# nano.net
KiCad netlist of a schematic drawn in EAGLE
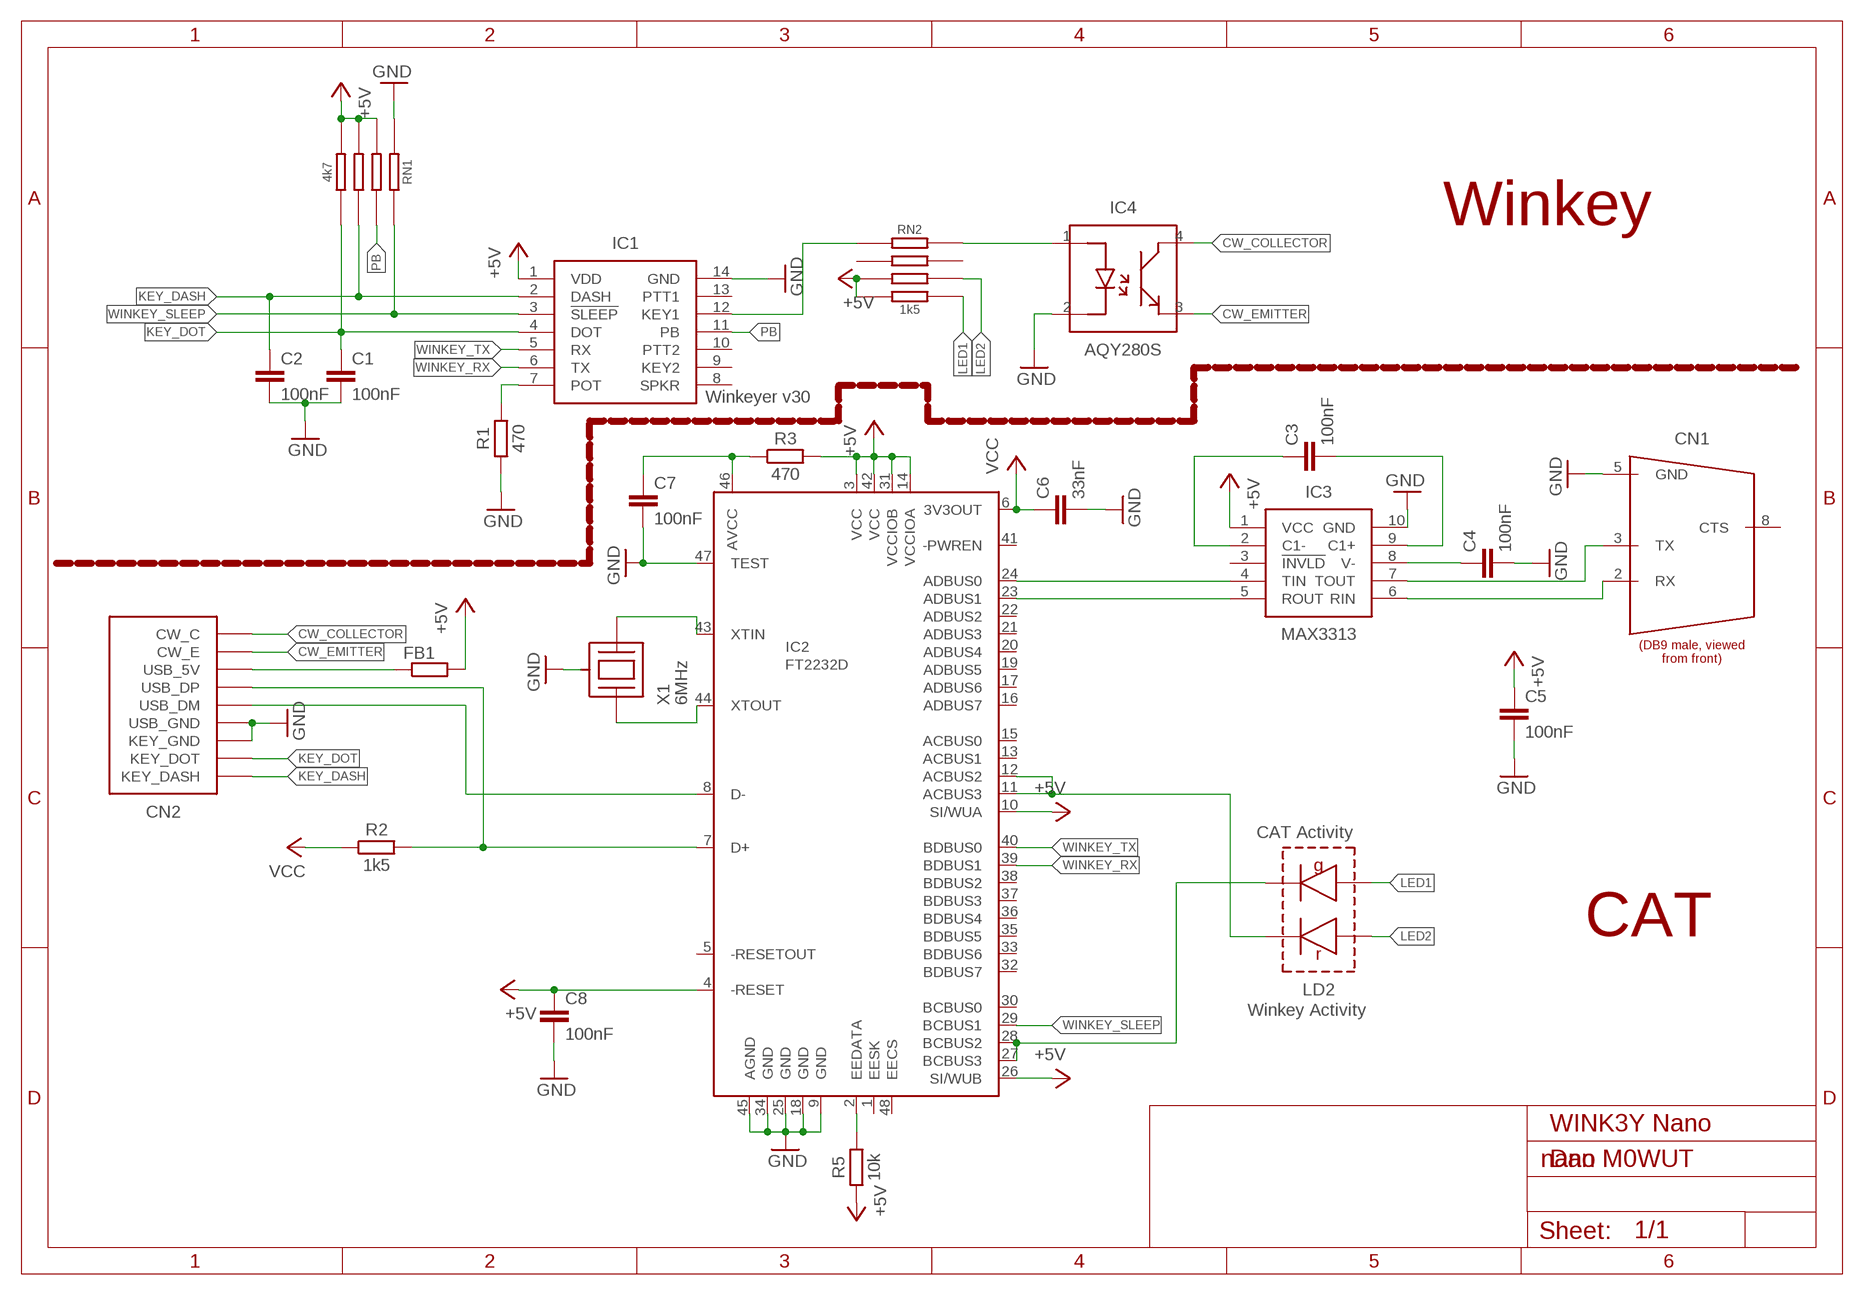
[diagram p0: schematic, sheet 1]

(export (version "E")
  (design (tool "Eeschema 10.0.6"))
  (components
    (comp (ref "C1")
      (value "100nF")
      (footprint "eagle-import:C0402")
      (libsource (lib "eagle-import") (part "C-EUC0402"))
    )
    (comp (ref "C2")
      (value "100nF")
      (footprint "eagle-import:C0402")
      (libsource (lib "eagle-import") (part "C-EUC0402"))
    )
    (comp (ref "C3")
      (value "100nF")
      (footprint "eagle-import:C0402")
      (libsource (lib "eagle-import") (part "C-EUC0402"))
    )
    (comp (ref "C4")
      (value "100nF")
      (footprint "eagle-import:C0402")
      (libsource (lib "eagle-import") (part "C-EUC0402"))
    )
    (comp (ref "C5")
      (value "100nF")
      (footprint "eagle-import:C0402")
      (libsource (lib "eagle-import") (part "C-EUC0402"))
    )
    (comp (ref "C6")
      (value "33nF")
      (footprint "eagle-import:C0402")
      (libsource (lib "eagle-import") (part "C-EUC0402"))
    )
    (comp (ref "C7")
      (value "100nF")
      (footprint "eagle-import:C0402")
      (libsource (lib "eagle-import") (part "C-EUC0402"))
    )
    (comp (ref "C8")
      (value "100nF")
      (footprint "eagle-import:C0402")
      (libsource (lib "eagle-import") (part "C-EUC0402"))
    )
    (comp (ref "CN1")
      (value "CONN_DB9_MALE")
      (footprint "eagle-import:CONN_DB9")
      (libsource (lib "eagle-import") (part "CONN_DB9_MALE"))
    )
    (comp (ref "CN2")
      (value "CONN_WINK3Y")
      (footprint "eagle-import:CONN_2MMX9")
      (libsource (lib "eagle-import") (part "CONN_WINK3Y"))
    )
    (comp (ref "FB1")
      (value "R-EU_R0805")
      (footprint "eagle-import:R0805")
      (libsource (lib "eagle-import") (part "resistor_R-EU_R0805"))
    )
    (comp (ref "IC1")
      (value "WINKEYER")
      (footprint "eagle-import:SO14")
      (libsource (lib "eagle-import") (part "WINKEYER"))
    )
    (comp (ref "IC2")
      (value "FT2232D")
      (footprint "eagle-import:QFP48-7X7")
      (libsource (lib "eagle-import") (part "FT2232D"))
    )
    (comp (ref "IC3")
      (value "IC_MAX3313")
      (footprint "eagle-import:IC_UMAX10")
      (libsource (lib "eagle-import") (part "IC_MAX3313"))
    )
    (comp (ref "IC4")
      (value "IC_AQY280S")
      (footprint "eagle-import:IC_AQY280S")
      (libsource (lib "eagle-import") (part "IC_AQY280S"))
    )
    (comp (ref "LD2")
      (value "LED_KINGBRIGHT_KPTB")
      (footprint "eagle-import:LED_KINGBRIGHT_KPTB")
      (libsource (lib "eagle-import") (part "LED_KINGBRIGHT_KPTB"))
    )
    (comp (ref "R1")
      (value "470")
      (footprint "eagle-import:R0402")
      (libsource (lib "eagle-import") (part "R-EU_R0402"))
    )
    (comp (ref "R2")
      (value "1k5")
      (footprint "eagle-import:R0402")
      (libsource (lib "eagle-import") (part "R-EU_R0402"))
    )
    (comp (ref "R3")
      (value "470")
      (footprint "eagle-import:R0402")
      (libsource (lib "eagle-import") (part "R-EU_R0402"))
    )
    (comp (ref "R5")
      (value "10k")
      (footprint "eagle-import:R0402")
      (libsource (lib "eagle-import") (part "R-EU_R0402"))
    )
    (comp (ref "RN1")
      (value "4k7")
      (footprint "eagle-import:R_BOURNS_CAY16-J4")
      (libsource (lib "eagle-import") (part "R_BOURNS_CAY16-J4"))
    )
    (comp (ref "RN2")
      (value "1k5")
      (footprint "eagle-import:R_BOURNS_CAY16-J4")
      (libsource (lib "eagle-import") (part "R_BOURNS_CAY16-J4"))
    )
    (comp (ref "X1")
      (value "6MHz")
      (footprint "eagle-import:XTAL_MURATA_3-PIN-RES")
      (libsource (lib "eagle-import") (part "XTAL_MURATA_3-PIN-RES"))
    )
  )
  (nets
    (net (code "1") (name "+5V") (class "Default")
      (node (ref "C5") (pin "1") (pinfunction "1_1") (pintype "passive"))
      (node (ref "C8") (pin "1") (pinfunction "1_1") (pintype "passive"))
      (node (ref "FB1") (pin "2") (pinfunction "2_2") (pintype "passive"))
      (node (ref "IC1") (pin "1") (pinfunction "VDD_1") (pintype "bidirectional"))
      (node (ref "IC2") (pin "10") (pinfunction "SI/WUA_10") (pintype "bidirectional"))
      (node (ref "IC2") (pin "14") (pinfunction "VCCIOA_14") (pintype "power_in"))
      (node (ref "IC2") (pin "26") (pinfunction "SI/WUB_26") (pintype "bidirectional"))
      (node (ref "IC2") (pin "3") (pinfunction "VCC_3") (pintype "power_in"))
      (node (ref "IC2") (pin "31") (pinfunction "VCCIOB_31") (pintype "power_in"))
      (node (ref "IC2") (pin "4") (pinfunction "-RESET_4") (pintype "input"))
      (node (ref "IC2") (pin "42") (pinfunction "VCC_42") (pintype "power_in"))
      (node (ref "IC3") (pin "1") (pinfunction "VCC_1") (pintype "bidirectional"))
      (node (ref "R3") (pin "2") (pinfunction "2_2") (pintype "passive"))
      (node (ref "R5") (pin "1") (pinfunction "1_1") (pintype "passive"))
      (node (ref "RN1") (pin "2") (pinfunction "2_2") (pintype "bidirectional"))
      (node (ref "RN1") (pin "3") (pinfunction "3_3") (pintype "bidirectional"))
      (node (ref "RN1") (pin "4") (pinfunction "4_4") (pintype "bidirectional"))
      (node (ref "RN2") (pin "3") (pinfunction "3_3") (pintype "bidirectional"))
      (node (ref "RN2") (pin "4") (pinfunction "4_4") (pintype "bidirectional"))
    )
    (net (code "2") (name "CW_COLLECTOR") (class "Default")
      (node (ref "CN2") (pin "CW_COLLECTOR") (pinfunction "CW_C_CW_COLLECTOR") (pintype "bidirectional"))
      (node (ref "IC4") (pin "4") (pinfunction "COLLECTOR_4") (pintype "bidirectional"))
    )
    (net (code "3") (name "CW_EMITTER") (class "Default")
      (node (ref "CN2") (pin "CW_EMITTER") (pinfunction "CW_E_CW_EMITTER") (pintype "bidirectional"))
      (node (ref "IC4") (pin "3") (pinfunction "EMITTER_3") (pintype "bidirectional"))
    )
    (net (code "4") (name "GND") (class "Default")
      (node (ref "C1") (pin "2") (pinfunction "2_2") (pintype "passive"))
      (node (ref "C2") (pin "2") (pinfunction "2_2") (pintype "passive"))
      (node (ref "C4") (pin "2") (pinfunction "2_2") (pintype "passive"))
      (node (ref "C5") (pin "2") (pinfunction "2_2") (pintype "passive"))
      (node (ref "C6") (pin "2") (pinfunction "2_2") (pintype "passive"))
      (node (ref "C7") (pin "2") (pinfunction "2_2") (pintype "passive"))
      (node (ref "C8") (pin "2") (pinfunction "2_2") (pintype "passive"))
      (node (ref "CN1") (pin "5") (pinfunction "GND_5") (pintype "bidirectional"))
      (node (ref "CN2") (pin "KEY_GND") (pinfunction "KEY_GND_KEY_GND") (pintype "bidirectional"))
      (node (ref "CN2") (pin "USB_GND") (pinfunction "USB_GND_USB_GND") (pintype "bidirectional"))
      (node (ref "IC1") (pin "14") (pinfunction "GND_14") (pintype "bidirectional"))
      (node (ref "IC2") (pin "18") (pinfunction "GND_18") (pintype "power_in"))
      (node (ref "IC2") (pin "25") (pinfunction "GND_25") (pintype "power_in"))
      (node (ref "IC2") (pin "34") (pinfunction "GND_34") (pintype "power_in"))
      (node (ref "IC2") (pin "45") (pinfunction "AGND_45") (pintype "power_in"))
      (node (ref "IC2") (pin "47") (pinfunction "TEST_47") (pintype "input"))
      (node (ref "IC2") (pin "9") (pinfunction "GND_9") (pintype "power_in"))
      (node (ref "IC3") (pin "10") (pinfunction "GND_10") (pintype "bidirectional"))
      (node (ref "IC4") (pin "2") (pinfunction "CATHODE_2") (pintype "bidirectional"))
      (node (ref "R1") (pin "1") (pinfunction "1_1") (pintype "passive"))
      (node (ref "RN1") (pin "1") (pinfunction "1_1") (pintype "bidirectional"))
      (node (ref "X1") (pin "GND") (pinfunction "CAN_GND") (pintype "bidirectional"))
    )
    (net (code "5") (name "KEY_DASH") (class "Default")
      (node (ref "C2") (pin "1") (pinfunction "1_1") (pintype "passive"))
      (node (ref "CN2") (pin "KEY_DASH") (pinfunction "KEY_DASH_KEY_DASH") (pintype "bidirectional"))
      (node (ref "IC1") (pin "2") (pinfunction "DASH_2") (pintype "bidirectional"))
      (node (ref "RN1") (pin "3A") (pinfunction "3A_3A") (pintype "bidirectional"))
    )
    (net (code "6") (name "KEY_DOT") (class "Default")
      (node (ref "C1") (pin "1") (pinfunction "1_1") (pintype "passive"))
      (node (ref "CN2") (pin "KEY_DOT") (pinfunction "KEY_DOT_KEY_DOT") (pintype "bidirectional"))
      (node (ref "IC1") (pin "4") (pinfunction "DOT_4") (pintype "bidirectional"))
      (node (ref "RN1") (pin "4A") (pinfunction "4A_4A") (pintype "bidirectional"))
    )
    (net (code "7") (name "LED1") (class "Default")
      (node (ref "LD2") (pin "3") (pinfunction "G_ANODE_3") (pintype "bidirectional"))
      (node (ref "RN2") (pin "4A") (pinfunction "4A_4A") (pintype "bidirectional"))
    )
    (net (code "8") (name "LED2") (class "Default")
      (node (ref "LD2") (pin "1") (pinfunction "R_ANODE_1") (pintype "bidirectional"))
      (node (ref "RN2") (pin "3A") (pinfunction "3A_3A") (pintype "bidirectional"))
    )
    (net (code "9") (name "Net-(CN1-RX)") (class "Default")
      (node (ref "CN1") (pin "2") (pinfunction "RX_2") (pintype "bidirectional"))
      (node (ref "IC3") (pin "6") (pinfunction "RIN_6") (pintype "bidirectional"))
    )
    (net (code "10") (name "Net-(CN1-TX)") (class "Default")
      (node (ref "CN1") (pin "3") (pinfunction "TX_3") (pintype "bidirectional"))
      (node (ref "IC3") (pin "7") (pinfunction "TOUT_7") (pintype "bidirectional"))
    )
    (net (code "11") (name "Net-(CN2-PadUSB_5V)") (class "Default")
      (node (ref "CN2") (pin "USB_5V") (pinfunction "USB_5V_USB_5V") (pintype "bidirectional"))
      (node (ref "FB1") (pin "1") (pinfunction "1_1") (pintype "passive"))
    )
    (net (code "12") (name "Net-(IC1-KEY1)") (class "Default")
      (node (ref "IC1") (pin "12") (pinfunction "KEY1_12") (pintype "bidirectional"))
      (node (ref "RN2") (pin "1") (pinfunction "1_1") (pintype "bidirectional"))
    )
    (net (code "13") (name "Net-(IC1-POT)") (class "Default")
      (node (ref "IC1") (pin "7") (pinfunction "POT_7") (pintype "bidirectional"))
      (node (ref "R1") (pin "2") (pinfunction "2_2") (pintype "passive"))
    )
    (net (code "14") (name "Net-(IC2-ACBUS2)") (class "Default")
      (node (ref "IC2") (pin "11") (pinfunction "ACBUS3_11") (pintype "bidirectional"))
      (node (ref "IC2") (pin "12") (pinfunction "ACBUS2_12") (pintype "bidirectional"))
      (node (ref "LD2") (pin "2") (pinfunction "R_CATHODE_2") (pintype "bidirectional"))
    )
    (net (code "15") (name "Net-(IC2-ADBUS0)") (class "Default")
      (node (ref "IC2") (pin "24") (pinfunction "ADBUS0_24") (pintype "bidirectional"))
      (node (ref "IC3") (pin "4") (pinfunction "TIN_4") (pintype "bidirectional"))
    )
    (net (code "16") (name "Net-(IC2-ADBUS1)") (class "Default")
      (node (ref "IC2") (pin "23") (pinfunction "ADBUS1_23") (pintype "bidirectional"))
      (node (ref "IC3") (pin "5") (pinfunction "ROUT_5") (pintype "bidirectional"))
    )
    (net (code "17") (name "Net-(IC2-AVCC)") (class "Default")
      (node (ref "C7") (pin "1") (pinfunction "1_1") (pintype "passive"))
      (node (ref "IC2") (pin "46") (pinfunction "AVCC_46") (pintype "power_in"))
      (node (ref "R3") (pin "1") (pinfunction "1_1") (pintype "passive"))
    )
    (net (code "18") (name "Net-(IC2-BCBUS2)") (class "Default")
      (node (ref "IC2") (pin "27") (pinfunction "BCBUS3_27") (pintype "bidirectional"))
      (node (ref "IC2") (pin "28") (pinfunction "BCBUS2_28") (pintype "bidirectional"))
      (node (ref "LD2") (pin "4") (pinfunction "G_CATHODE_4") (pintype "bidirectional"))
    )
    (net (code "19") (name "Net-(IC2-D+)") (class "Default")
      (node (ref "CN2") (pin "USB_DP") (pinfunction "USB_DP_USB_DP") (pintype "bidirectional"))
      (node (ref "IC2") (pin "7") (pinfunction "D+_7") (pintype "bidirectional"))
      (node (ref "R2") (pin "2") (pinfunction "2_2") (pintype "passive"))
    )
    (net (code "20") (name "Net-(IC2-D-)") (class "Default")
      (node (ref "CN2") (pin "USB_DM") (pinfunction "USB_DM_USB_DM") (pintype "bidirectional"))
      (node (ref "IC2") (pin "8") (pinfunction "D-_8") (pintype "bidirectional"))
    )
    (net (code "21") (name "Net-(IC2-EEDATA)") (class "Default")
      (node (ref "IC2") (pin "2") (pinfunction "EEDATA_2") (pintype "input"))
      (node (ref "R5") (pin "2") (pinfunction "2_2") (pintype "passive"))
    )
    (net (code "22") (name "Net-(IC2-XTIN)") (class "Default")
      (node (ref "IC2") (pin "43") (pinfunction "XTIN_43") (pintype "input"))
      (node (ref "X1") (pin "2") (pinfunction "XTAL2_2") (pintype "bidirectional"))
    )
    (net (code "23") (name "Net-(IC2-XTOUT)") (class "Default")
      (node (ref "IC2") (pin "44") (pinfunction "XTOUT_44") (pintype "output"))
      (node (ref "X1") (pin "1") (pinfunction "XTAL1_1") (pintype "bidirectional"))
    )
    (net (code "24") (name "Net-(IC3-C1+)") (class "Default")
      (node (ref "C3") (pin "2") (pinfunction "2_2") (pintype "passive"))
      (node (ref "IC3") (pin "9") (pinfunction "C1+_9") (pintype "bidirectional"))
    )
    (net (code "25") (name "Net-(IC3-C1-)") (class "Default")
      (node (ref "C3") (pin "1") (pinfunction "1_1") (pintype "passive"))
      (node (ref "IC3") (pin "2") (pinfunction "C1-_2") (pintype "bidirectional"))
    )
    (net (code "26") (name "Net-(IC3-V-)") (class "Default")
      (node (ref "C4") (pin "1") (pinfunction "1_1") (pintype "passive"))
      (node (ref "IC3") (pin "8") (pinfunction "V-_8") (pintype "bidirectional"))
    )
    (net (code "27") (name "Net-(IC4-ANODE)") (class "Default")
      (node (ref "IC4") (pin "1") (pinfunction "ANODE_1") (pintype "bidirectional"))
      (node (ref "RN2") (pin "1A") (pinfunction "1A_1A") (pintype "bidirectional"))
    )
    (net (code "28") (name "PB") (class "Default")
      (node (ref "IC1") (pin "11") (pinfunction "PB_11") (pintype "bidirectional"))
      (node (ref "RN1") (pin "2A") (pinfunction "2A_2A") (pintype "bidirectional"))
    )
    (net (code "29") (name "VCC") (class "Default")
      (node (ref "C6") (pin "1") (pinfunction "1_1") (pintype "passive"))
      (node (ref "IC2") (pin "6") (pinfunction "3V3OUT_6") (pintype "power_in"))
      (node (ref "R2") (pin "1") (pinfunction "1_1") (pintype "passive"))
    )
    (net (code "30") (name "WINKEY_RX") (class "Default")
      (node (ref "IC1") (pin "6") (pinfunction "TX_6") (pintype "bidirectional"))
      (node (ref "IC2") (pin "39") (pinfunction "BDBUS1_39") (pintype "bidirectional"))
    )
    (net (code "31") (name "WINKEY_SLEEP") (class "Default")
      (node (ref "IC1") (pin "3") (pinfunction "~{SLEEP}_3") (pintype "bidirectional"))
      (node (ref "IC2") (pin "29") (pinfunction "BCBUS1_29") (pintype "bidirectional"))
      (node (ref "RN1") (pin "1A") (pinfunction "1A_1A") (pintype "bidirectional"))
    )
    (net (code "32") (name "WINKEY_TX") (class "Default")
      (node (ref "IC1") (pin "5") (pinfunction "RX_5") (pintype "bidirectional"))
      (node (ref "IC2") (pin "40") (pinfunction "BDBUS0_40") (pintype "bidirectional"))
    )
    (net (code "33") (name "unconnected-(CN1-CTS-Pad8)") (class "Default")
      (node (ref "CN1") (pin "8") (pinfunction "CTS_8") (pintype "bidirectional"))
    )
    (net (code "34") (name "unconnected-(IC1-KEY2-Pad9)") (class "Default")
      (node (ref "IC1") (pin "9") (pinfunction "KEY2_9") (pintype "bidirectional"))
    )
    (net (code "35") (name "unconnected-(IC1-PTT1-Pad13)") (class "Default")
      (node (ref "IC1") (pin "13") (pinfunction "PTT1_13") (pintype "bidirectional"))
    )
    (net (code "36") (name "unconnected-(IC1-PTT2-Pad10)") (class "Default")
      (node (ref "IC1") (pin "10") (pinfunction "PTT2_10") (pintype "bidirectional"))
    )
    (net (code "37") (name "unconnected-(IC1-SPKR-Pad8)") (class "Default")
      (node (ref "IC1") (pin "8") (pinfunction "SPKR_8") (pintype "bidirectional"))
    )
    (net (code "38") (name "unconnected-(IC2--PWREN-Pad41)") (class "Default")
      (node (ref "IC2") (pin "41") (pinfunction "-PWREN_41") (pintype "output"))
    )
    (net (code "39") (name "unconnected-(IC2--RESETOUT-Pad5)") (class "Default")
      (node (ref "IC2") (pin "5") (pinfunction "-RESETOUT_5") (pintype "output"))
    )
    (net (code "40") (name "unconnected-(IC2-ACBUS0-Pad15)") (class "Default")
      (node (ref "IC2") (pin "15") (pinfunction "ACBUS0_15") (pintype "bidirectional"))
    )
    (net (code "41") (name "unconnected-(IC2-ACBUS1-Pad13)") (class "Default")
      (node (ref "IC2") (pin "13") (pinfunction "ACBUS1_13") (pintype "bidirectional"))
    )
    (net (code "42") (name "unconnected-(IC2-ADBUS2-Pad22)") (class "Default")
      (node (ref "IC2") (pin "22") (pinfunction "ADBUS2_22") (pintype "bidirectional"))
    )
    (net (code "43") (name "unconnected-(IC2-ADBUS3-Pad21)") (class "Default")
      (node (ref "IC2") (pin "21") (pinfunction "ADBUS3_21") (pintype "bidirectional"))
    )
    (net (code "44") (name "unconnected-(IC2-ADBUS4-Pad20)") (class "Default")
      (node (ref "IC2") (pin "20") (pinfunction "ADBUS4_20") (pintype "bidirectional"))
    )
    (net (code "45") (name "unconnected-(IC2-ADBUS5-Pad19)") (class "Default")
      (node (ref "IC2") (pin "19") (pinfunction "ADBUS5_19") (pintype "bidirectional"))
    )
    (net (code "46") (name "unconnected-(IC2-ADBUS6-Pad17)") (class "Default")
      (node (ref "IC2") (pin "17") (pinfunction "ADBUS6_17") (pintype "bidirectional"))
    )
    (net (code "47") (name "unconnected-(IC2-ADBUS7-Pad16)") (class "Default")
      (node (ref "IC2") (pin "16") (pinfunction "ADBUS7_16") (pintype "bidirectional"))
    )
    (net (code "48") (name "unconnected-(IC2-BCBUS0-Pad30)") (class "Default")
      (node (ref "IC2") (pin "30") (pinfunction "BCBUS0_30") (pintype "bidirectional"))
    )
    (net (code "49") (name "unconnected-(IC2-BDBUS2-Pad38)") (class "Default")
      (node (ref "IC2") (pin "38") (pinfunction "BDBUS2_38") (pintype "bidirectional"))
    )
    (net (code "50") (name "unconnected-(IC2-BDBUS3-Pad37)") (class "Default")
      (node (ref "IC2") (pin "37") (pinfunction "BDBUS3_37") (pintype "bidirectional"))
    )
    (net (code "51") (name "unconnected-(IC2-BDBUS4-Pad36)") (class "Default")
      (node (ref "IC2") (pin "36") (pinfunction "BDBUS4_36") (pintype "bidirectional"))
    )
    (net (code "52") (name "unconnected-(IC2-BDBUS5-Pad35)") (class "Default")
      (node (ref "IC2") (pin "35") (pinfunction "BDBUS5_35") (pintype "bidirectional"))
    )
    (net (code "53") (name "unconnected-(IC2-BDBUS6-Pad33)") (class "Default")
      (node (ref "IC2") (pin "33") (pinfunction "BDBUS6_33") (pintype "bidirectional"))
    )
    (net (code "54") (name "unconnected-(IC2-BDBUS7-Pad32)") (class "Default")
      (node (ref "IC2") (pin "32") (pinfunction "BDBUS7_32") (pintype "bidirectional"))
    )
    (net (code "55") (name "unconnected-(IC2-EECS-Pad48)") (class "Default")
      (node (ref "IC2") (pin "48") (pinfunction "EECS_48") (pintype "output"))
    )
    (net (code "56") (name "unconnected-(IC2-EESK-Pad1)") (class "Default")
      (node (ref "IC2") (pin "1") (pinfunction "EESK_1") (pintype "output"))
    )
    (net (code "57") (name "unconnected-(IC3-~{INVLD}-Pad3)") (class "Default")
      (node (ref "IC3") (pin "3") (pinfunction "~{INVLD}_3") (pintype "bidirectional"))
    )
    (net (code "58") (name "unconnected-(RN2-Pad2)") (class "Default")
      (node (ref "RN2") (pin "2") (pinfunction "2_2") (pintype "bidirectional"))
    )
    (net (code "59") (name "unconnected-(RN2-Pad2A)") (class "Default")
      (node (ref "RN2") (pin "2A") (pinfunction "2A_2A") (pintype "bidirectional"))
    )
  )
)
